# CPM_Pmod.net
KiCad netlist of a schematic drawn in EAGLE
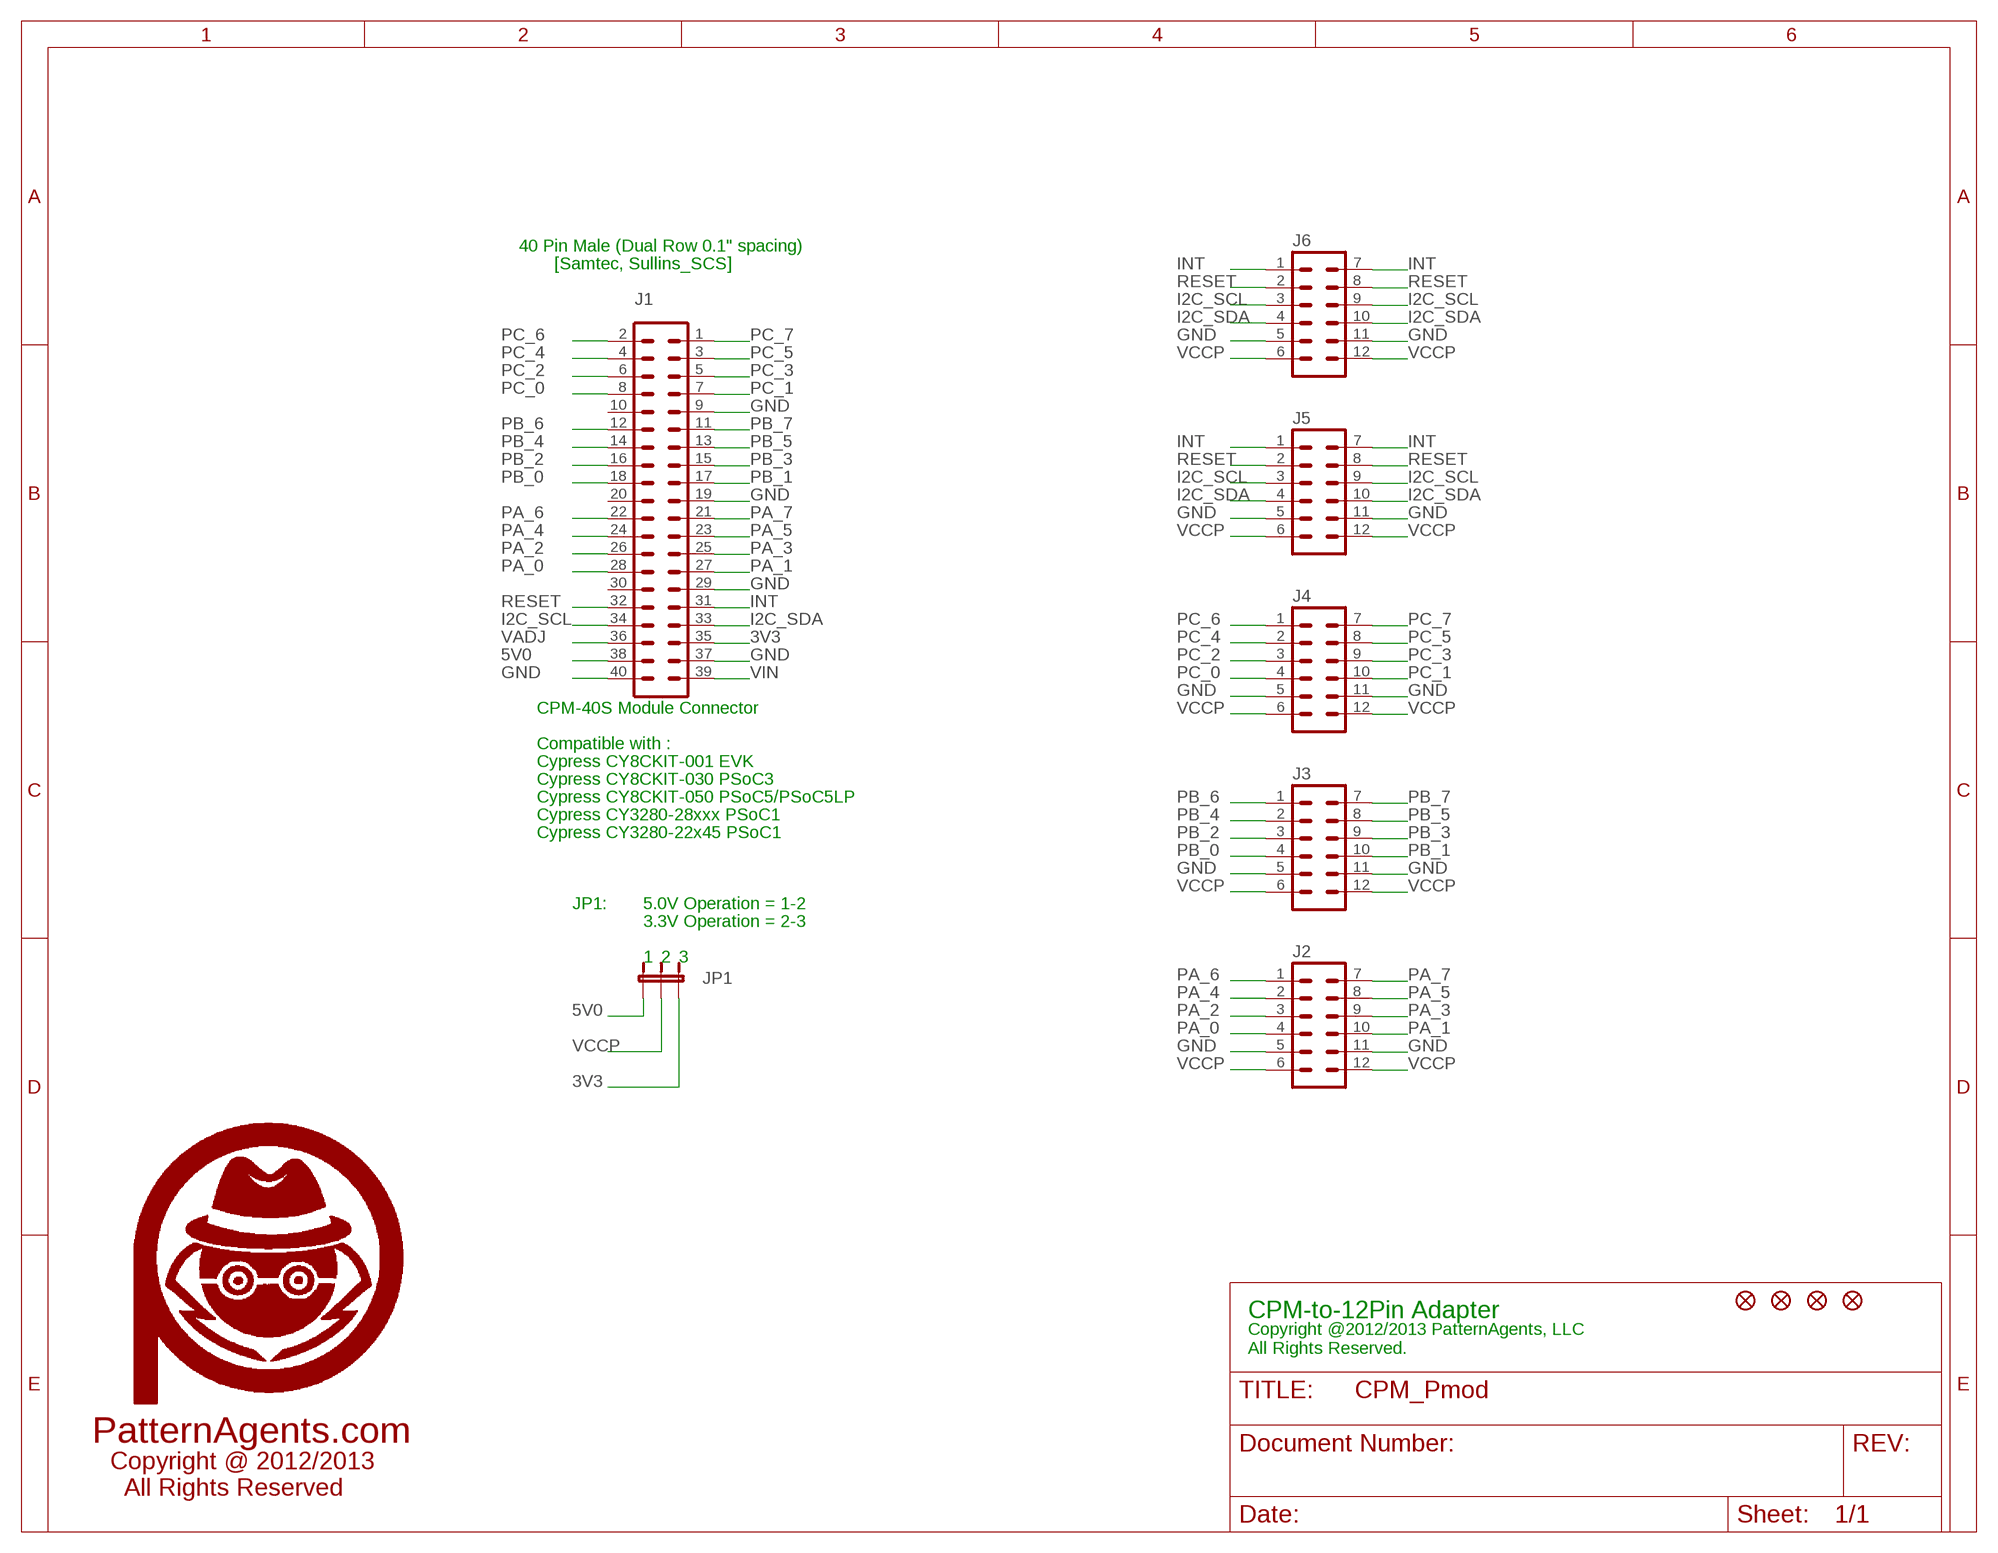
[diagram p0: schematic, sheet 1]

(export (version "E")
  (design (tool "Eeschema 10.0.6"))
  (components
    (comp (ref "J1")
      (value "SULLINS_SCS")
      (footprint "eagle-import:MA20-2")
      (fields (field (name "MF") "Sullins") (field (name "MPN") "PBC20DBAN"))
      (libsource (lib "eagle-import") (part "MA20-2"))
    )
    (comp (ref "J2")
      (value "MA06-2-PMOD")
      (footprint "eagle-import:MA06-2-PMOD")
      (libsource (lib "eagle-import") (part "MA06-2-PMOD"))
    )
    (comp (ref "J3")
      (value "MA06-2-PMOD")
      (footprint "eagle-import:MA06-2-PMOD")
      (libsource (lib "eagle-import") (part "MA06-2-PMOD"))
    )
    (comp (ref "J4")
      (value "MA06-2-PMOD")
      (footprint "eagle-import:MA06-2-PMOD")
      (libsource (lib "eagle-import") (part "MA06-2-PMOD"))
    )
    (comp (ref "J5")
      (value "MA06-2-PMOD")
      (footprint "eagle-import:MA06-2-PMOD")
      (libsource (lib "eagle-import") (part "MA06-2-PMOD"))
    )
    (comp (ref "J6")
      (value "MA06-2-PMOD")
      (footprint "eagle-import:MA06-2-PMOD")
      (libsource (lib "eagle-import") (part "MA06-2-PMOD"))
    )
    (comp (ref "JP1")
      (value "JUMPER-3PTH")
      (footprint "eagle-import:1X03")
      (libsource (lib "eagle-import") (part "JUMPER-3PTH"))
    )
    (comp (ref "JP2")
      (value "FIDUCIAL1.5X3")
      (footprint "eagle-import:FIDUCIAL-1.5X3")
      (libsource (lib "eagle-import") (part "FIDUCIAL1.5X3"))
    )
    (comp (ref "JP3")
      (value "FIDUCIAL1.5X3")
      (footprint "eagle-import:FIDUCIAL-1.5X3")
      (libsource (lib "eagle-import") (part "FIDUCIAL1.5X3"))
    )
    (comp (ref "JP4")
      (value "FIDUCIAL1.5X3")
      (footprint "eagle-import:FIDUCIAL-1.5X3")
      (libsource (lib "eagle-import") (part "FIDUCIAL1.5X3"))
    )
    (comp (ref "JP5")
      (value "FIDUCIAL1.5X3")
      (footprint "eagle-import:FIDUCIAL-1.5X3")
      (libsource (lib "eagle-import") (part "FIDUCIAL1.5X3"))
    )
    (comp (ref "U$1")
      (value "LOGO_PA_AGENTLARGE")
      (footprint "eagle-import:LOGO_PA_AGENT_LARGE")
      (libsource (lib "eagle-import") (part "LOGO_PA_AGENTLARGE"))
    )
  )
  (nets
    (net (code "1") (name "/3V3") (class "Default")
      (node (ref "J1") (pin "35") (pinfunction "35_35") (pintype "passive"))
      (node (ref "JP1") (pin "3") (pinfunction "3_3") (pintype "passive"))
    )
    (net (code "2") (name "/5V0") (class "Default")
      (node (ref "J1") (pin "38") (pinfunction "38_38") (pintype "passive"))
      (node (ref "JP1") (pin "1") (pinfunction "1_1") (pintype "passive"))
    )
    (net (code "3") (name "/GND") (class "Default")
      (node (ref "J1") (pin "19") (pinfunction "19_19") (pintype "passive"))
      (node (ref "J1") (pin "29") (pinfunction "29_29") (pintype "passive"))
      (node (ref "J1") (pin "37") (pinfunction "37_37") (pintype "passive"))
      (node (ref "J1") (pin "40") (pinfunction "40_40") (pintype "passive"))
      (node (ref "J1") (pin "9") (pinfunction "9_9") (pintype "passive"))
      (node (ref "J2") (pin "11") (pinfunction "11_11") (pintype "passive"))
      (node (ref "J2") (pin "5") (pinfunction "5_5") (pintype "passive"))
      (node (ref "J3") (pin "11") (pinfunction "11_11") (pintype "passive"))
      (node (ref "J3") (pin "5") (pinfunction "5_5") (pintype "passive"))
      (node (ref "J4") (pin "11") (pinfunction "11_11") (pintype "passive"))
      (node (ref "J4") (pin "5") (pinfunction "5_5") (pintype "passive"))
      (node (ref "J5") (pin "11") (pinfunction "11_11") (pintype "passive"))
      (node (ref "J5") (pin "5") (pinfunction "5_5") (pintype "passive"))
      (node (ref "J6") (pin "11") (pinfunction "11_11") (pintype "passive"))
      (node (ref "J6") (pin "5") (pinfunction "5_5") (pintype "passive"))
    )
    (net (code "4") (name "/I2C_SCL") (class "Default")
      (node (ref "J1") (pin "34") (pinfunction "34_34") (pintype "passive"))
      (node (ref "J5") (pin "3") (pinfunction "3_3") (pintype "passive"))
      (node (ref "J5") (pin "9") (pinfunction "9_9") (pintype "passive"))
      (node (ref "J6") (pin "3") (pinfunction "3_3") (pintype "passive"))
      (node (ref "J6") (pin "9") (pinfunction "9_9") (pintype "passive"))
    )
    (net (code "5") (name "/I2C_SDA") (class "Default")
      (node (ref "J1") (pin "33") (pinfunction "33_33") (pintype "passive"))
      (node (ref "J5") (pin "10") (pinfunction "10_10") (pintype "passive"))
      (node (ref "J5") (pin "4") (pinfunction "4_4") (pintype "passive"))
      (node (ref "J6") (pin "10") (pinfunction "10_10") (pintype "passive"))
      (node (ref "J6") (pin "4") (pinfunction "4_4") (pintype "passive"))
    )
    (net (code "6") (name "/INT") (class "Default")
      (node (ref "J1") (pin "31") (pinfunction "31_31") (pintype "passive"))
      (node (ref "J5") (pin "1") (pinfunction "1_1") (pintype "passive"))
      (node (ref "J5") (pin "7") (pinfunction "7_7") (pintype "passive"))
      (node (ref "J6") (pin "1") (pinfunction "1_1") (pintype "passive"))
      (node (ref "J6") (pin "7") (pinfunction "7_7") (pintype "passive"))
    )
    (net (code "7") (name "/PA_0") (class "Default")
      (node (ref "J1") (pin "28") (pinfunction "28_28") (pintype "passive"))
      (node (ref "J2") (pin "4") (pinfunction "4_4") (pintype "passive"))
    )
    (net (code "8") (name "/PA_1") (class "Default")
      (node (ref "J1") (pin "27") (pinfunction "27_27") (pintype "passive"))
      (node (ref "J2") (pin "10") (pinfunction "10_10") (pintype "passive"))
    )
    (net (code "9") (name "/PA_2") (class "Default")
      (node (ref "J1") (pin "26") (pinfunction "26_26") (pintype "passive"))
      (node (ref "J2") (pin "3") (pinfunction "3_3") (pintype "passive"))
    )
    (net (code "10") (name "/PA_3") (class "Default")
      (node (ref "J1") (pin "25") (pinfunction "25_25") (pintype "passive"))
      (node (ref "J2") (pin "9") (pinfunction "9_9") (pintype "passive"))
    )
    (net (code "11") (name "/PA_4") (class "Default")
      (node (ref "J1") (pin "24") (pinfunction "24_24") (pintype "passive"))
      (node (ref "J2") (pin "2") (pinfunction "2_2") (pintype "passive"))
    )
    (net (code "12") (name "/PA_5") (class "Default")
      (node (ref "J1") (pin "23") (pinfunction "23_23") (pintype "passive"))
      (node (ref "J2") (pin "8") (pinfunction "8_8") (pintype "passive"))
    )
    (net (code "13") (name "/PA_6") (class "Default")
      (node (ref "J1") (pin "22") (pinfunction "22_22") (pintype "passive"))
      (node (ref "J2") (pin "1") (pinfunction "1_1") (pintype "passive"))
    )
    (net (code "14") (name "/PA_7") (class "Default")
      (node (ref "J1") (pin "21") (pinfunction "21_21") (pintype "passive"))
      (node (ref "J2") (pin "7") (pinfunction "7_7") (pintype "passive"))
    )
    (net (code "15") (name "/PB_0") (class "Default")
      (node (ref "J1") (pin "18") (pinfunction "18_18") (pintype "passive"))
      (node (ref "J3") (pin "4") (pinfunction "4_4") (pintype "passive"))
    )
    (net (code "16") (name "/PB_1") (class "Default")
      (node (ref "J1") (pin "17") (pinfunction "17_17") (pintype "passive"))
      (node (ref "J3") (pin "10") (pinfunction "10_10") (pintype "passive"))
    )
    (net (code "17") (name "/PB_2") (class "Default")
      (node (ref "J1") (pin "16") (pinfunction "16_16") (pintype "passive"))
      (node (ref "J3") (pin "3") (pinfunction "3_3") (pintype "passive"))
    )
    (net (code "18") (name "/PB_3") (class "Default")
      (node (ref "J1") (pin "15") (pinfunction "15_15") (pintype "passive"))
      (node (ref "J3") (pin "9") (pinfunction "9_9") (pintype "passive"))
    )
    (net (code "19") (name "/PB_4") (class "Default")
      (node (ref "J1") (pin "14") (pinfunction "14_14") (pintype "passive"))
      (node (ref "J3") (pin "2") (pinfunction "2_2") (pintype "passive"))
    )
    (net (code "20") (name "/PB_5") (class "Default")
      (node (ref "J1") (pin "13") (pinfunction "13_13") (pintype "passive"))
      (node (ref "J3") (pin "8") (pinfunction "8_8") (pintype "passive"))
    )
    (net (code "21") (name "/PB_6") (class "Default")
      (node (ref "J1") (pin "12") (pinfunction "12_12") (pintype "passive"))
      (node (ref "J3") (pin "1") (pinfunction "1_1") (pintype "passive"))
    )
    (net (code "22") (name "/PB_7") (class "Default")
      (node (ref "J1") (pin "11") (pinfunction "11_11") (pintype "passive"))
      (node (ref "J3") (pin "7") (pinfunction "7_7") (pintype "passive"))
    )
    (net (code "23") (name "/PC_0") (class "Default")
      (node (ref "J1") (pin "8") (pinfunction "8_8") (pintype "passive"))
      (node (ref "J4") (pin "4") (pinfunction "4_4") (pintype "passive"))
    )
    (net (code "24") (name "/PC_1") (class "Default")
      (node (ref "J1") (pin "7") (pinfunction "7_7") (pintype "passive"))
      (node (ref "J4") (pin "10") (pinfunction "10_10") (pintype "passive"))
    )
    (net (code "25") (name "/PC_2") (class "Default")
      (node (ref "J1") (pin "6") (pinfunction "6_6") (pintype "passive"))
      (node (ref "J4") (pin "3") (pinfunction "3_3") (pintype "passive"))
    )
    (net (code "26") (name "/PC_3") (class "Default")
      (node (ref "J1") (pin "5") (pinfunction "5_5") (pintype "passive"))
      (node (ref "J4") (pin "9") (pinfunction "9_9") (pintype "passive"))
    )
    (net (code "27") (name "/PC_4") (class "Default")
      (node (ref "J1") (pin "4") (pinfunction "4_4") (pintype "passive"))
      (node (ref "J4") (pin "2") (pinfunction "2_2") (pintype "passive"))
    )
    (net (code "28") (name "/PC_5") (class "Default")
      (node (ref "J1") (pin "3") (pinfunction "3_3") (pintype "passive"))
      (node (ref "J4") (pin "8") (pinfunction "8_8") (pintype "passive"))
    )
    (net (code "29") (name "/PC_6") (class "Default")
      (node (ref "J1") (pin "2") (pinfunction "2_2") (pintype "passive"))
      (node (ref "J4") (pin "1") (pinfunction "1_1") (pintype "passive"))
    )
    (net (code "30") (name "/PC_7") (class "Default")
      (node (ref "J1") (pin "1") (pinfunction "1_1") (pintype "passive"))
      (node (ref "J4") (pin "7") (pinfunction "7_7") (pintype "passive"))
    )
    (net (code "31") (name "/RESET") (class "Default")
      (node (ref "J1") (pin "32") (pinfunction "32_32") (pintype "passive"))
      (node (ref "J5") (pin "2") (pinfunction "2_2") (pintype "passive"))
      (node (ref "J5") (pin "8") (pinfunction "8_8") (pintype "passive"))
      (node (ref "J6") (pin "2") (pinfunction "2_2") (pintype "passive"))
      (node (ref "J6") (pin "8") (pinfunction "8_8") (pintype "passive"))
    )
    (net (code "32") (name "/VADJ") (class "Default")
      (node (ref "J1") (pin "36") (pinfunction "36_36") (pintype "passive"))
    )
    (net (code "33") (name "/VCCP") (class "Default")
      (node (ref "J2") (pin "12") (pinfunction "12_12") (pintype "passive"))
      (node (ref "J2") (pin "6") (pinfunction "6_6") (pintype "passive"))
      (node (ref "J3") (pin "12") (pinfunction "12_12") (pintype "passive"))
      (node (ref "J3") (pin "6") (pinfunction "6_6") (pintype "passive"))
      (node (ref "J4") (pin "12") (pinfunction "12_12") (pintype "passive"))
      (node (ref "J4") (pin "6") (pinfunction "6_6") (pintype "passive"))
      (node (ref "J5") (pin "12") (pinfunction "12_12") (pintype "passive"))
      (node (ref "J5") (pin "6") (pinfunction "6_6") (pintype "passive"))
      (node (ref "J6") (pin "12") (pinfunction "12_12") (pintype "passive"))
      (node (ref "J6") (pin "6") (pinfunction "6_6") (pintype "passive"))
      (node (ref "JP1") (pin "2") (pinfunction "2_2") (pintype "passive"))
    )
    (net (code "34") (name "/VIN") (class "Default")
      (node (ref "J1") (pin "39") (pinfunction "39_39") (pintype "passive"))
    )
    (net (code "35") (name "unconnected-(J1-Pad10)") (class "Default")
      (node (ref "J1") (pin "10") (pinfunction "10_10") (pintype "passive"))
    )
    (net (code "36") (name "unconnected-(J1-Pad20)") (class "Default")
      (node (ref "J1") (pin "20") (pinfunction "20_20") (pintype "passive"))
    )
    (net (code "37") (name "unconnected-(J1-Pad30)") (class "Default")
      (node (ref "J1") (pin "30") (pinfunction "30_30") (pintype "passive"))
    )
  )
)
